# 2_-_Sense2GoL_V1_2_Main_Board.net
KiCad netlist of a schematic drawn in Altium Designer
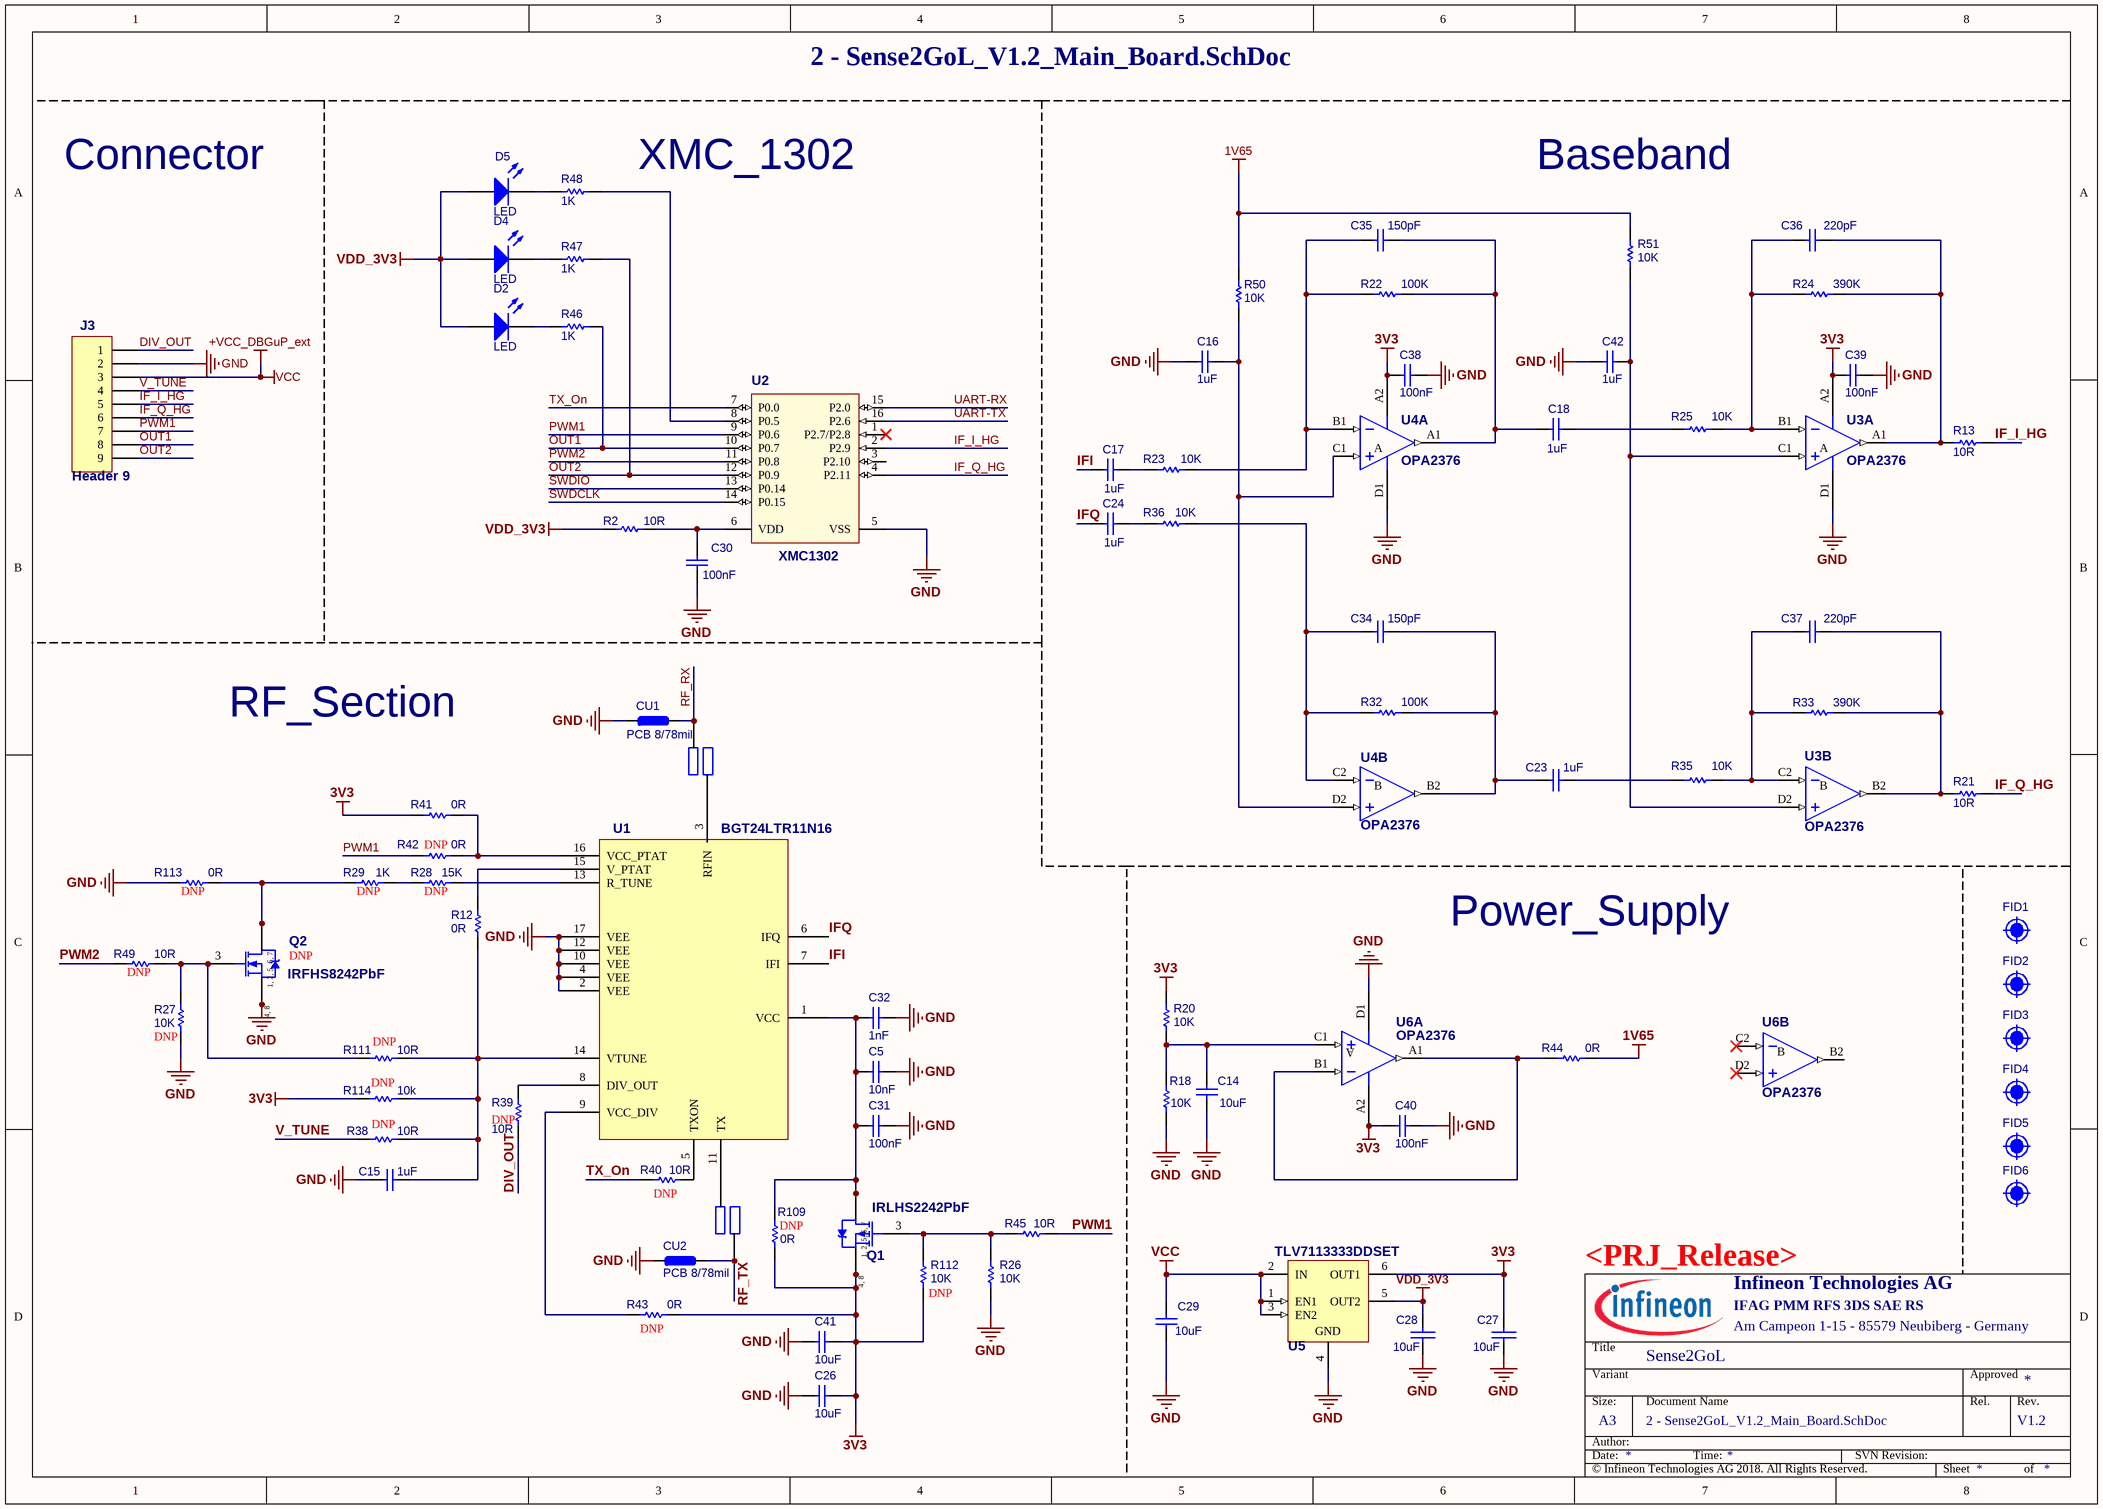
[diagram p0: 2 - Sense2GoL_V1.2_Main_Board.SchDoc]

(export (version "E")
  (design (tool "Eeschema 10.0.6"))
  (components
    (comp (ref "C5")
      (value "10nF")
      (footprint "C_0201")
      (description "Capacitor")
      (fields (field (name "Comment") "Cap") (field (name "PUBLISHER") "Altium Limited"))
      (libsource (lib "Miscellaneous Devices") (part "Cap"))
    )
    (comp (ref "C14")
      (value "10uF")
      (footprint "0402_DURAC")
      (description "Capacitor")
      (fields (field (name "Comment") "Cap") (field (name "PUBLISHER") "Altium Limited"))
      (libsource (lib "Miscellaneous Devices") (part "Cap"))
    )
    (comp (ref "C15")
      (value "1uF")
      (footprint "0402_DURAC")
      (description "Capacitor")
      (fields (field (name "Comment") "Cap") (field (name "PUBLISHER") "Altium Limited"))
      (libsource (lib "Miscellaneous Devices") (part "Cap"))
    )
    (comp (ref "C16")
      (value "1uF")
      (footprint "0402_DURAC")
      (description "Capacitor")
      (fields (field (name "Comment") "Cap") (field (name "PUBLISHER") "Altium Limited"))
      (libsource (lib "Miscellaneous Devices") (part "Cap"))
    )
    (comp (ref "C17")
      (value "1uF")
      (footprint "0402_DURAC")
      (description "Capacitor")
      (fields (field (name "Comment") "1µF") (field (name "PUBLISHER") "Altium Limited"))
      (libsource (lib "Miscellaneous Devices") (part "Cap"))
    )
    (comp (ref "C18")
      (value "1uF")
      (footprint "0402_DURAC")
      (description "Capacitor")
      (fields (field (name "Comment") "Cap") (field (name "PUBLISHER") "Altium Limited"))
      (libsource (lib "Miscellaneous Devices") (part "Cap"))
    )
    (comp (ref "C23")
      (value "1uF")
      (footprint "0402_DURAC")
      (description "Capacitor")
      (fields (field (name "Comment") "Cap") (field (name "PUBLISHER") "Altium Limited"))
      (libsource (lib "Miscellaneous Devices") (part "Cap"))
    )
    (comp (ref "C24")
      (value "1uF")
      (footprint "0402_DURAC")
      (description "Capacitor")
      (fields (field (name "Comment") "Cap") (field (name "PUBLISHER") "Altium Limited"))
      (libsource (lib "Miscellaneous Devices") (part "Cap"))
    )
    (comp (ref "C26")
      (value "10uF")
      (footprint "0402_DURAC")
      (description "Capacitor")
      (fields (field (name "Comment") "Cap") (field (name "PUBLISHER") "Altium Limited"))
      (libsource (lib "Miscellaneous Devices") (part "Cap"))
    )
    (comp (ref "C27")
      (value "10uF")
      (footprint "0402_DURAC")
      (description "Ceramic Capacitor X5R/X7R >= 10V")
      (fields (field (name "MANUFACTURER") "TDK") (field (name "Comment") "CAP-10uF-10V-20%-0603"))
      (libsource (lib "*") (part "CAP"))
    )
    (comp (ref "C28")
      (value "10uF")
      (footprint "0402_DURAC")
      (description "Ceramic Capacitor X5R/X7R >= 10V")
      (fields (field (name "MANUFACTURER") "TDK") (field (name "Comment") "CAP-10uF-10V-20%-0603"))
      (libsource (lib "*") (part "CAP"))
    )
    (comp (ref "C29")
      (value "10uF")
      (footprint "0402_DURAC")
      (description "Capacitor")
      (fields (field (name "MANUFACTURER") "TDK") (field (name "Comment") "CAP-1uF-25V-10%-0402"))
      (libsource (lib "Miscellaneous Devices") (part "Cap"))
    )
    (comp (ref "C30")
      (value "100nF")
      (footprint "C_0201")
      (description "Capacitor")
      (fields (field (name "Comment") "Cap") (field (name "PUBLISHER") "Altium Limited"))
      (libsource (lib "Miscellaneous Devices") (part "Cap"))
    )
    (comp (ref "C31")
      (value "100nF")
      (footprint "C_0201")
      (description "Capacitor")
      (fields (field (name "Comment") "Cap") (field (name "PUBLISHER") "Altium Limited"))
      (libsource (lib "Miscellaneous Devices") (part "Cap"))
    )
    (comp (ref "C32")
      (value "1nF")
      (footprint "C_0201")
      (description "Capacitor")
      (fields (field (name "Comment") "Cap") (field (name "PUBLISHER") "Altium Limited"))
      (libsource (lib "Miscellaneous Devices") (part "Cap"))
    )
    (comp (ref "C34")
      (value "150pF")
      (footprint "C_0201")
      (description "Capacitor")
      (fields (field (name "Comment") "Cap") (field (name "PUBLISHER") "Altium Limited"))
      (libsource (lib "Miscellaneous Devices") (part "Cap"))
    )
    (comp (ref "C35")
      (value "150pF")
      (footprint "C_0201")
      (description "Capacitor")
      (fields (field (name "Comment") "Cap") (field (name "PUBLISHER") "Altium Limited"))
      (libsource (lib "Miscellaneous Devices") (part "Cap"))
    )
    (comp (ref "C36")
      (value "220pF")
      (footprint "C_0201")
      (description "Capacitor")
      (fields (field (name "Comment") "Cap") (field (name "PUBLISHER") "Altium Limited"))
      (libsource (lib "Miscellaneous Devices") (part "Cap"))
    )
    (comp (ref "C37")
      (value "220pF")
      (footprint "C_0201")
      (description "Capacitor")
      (fields (field (name "Comment") "Cap") (field (name "PUBLISHER") "Altium Limited"))
      (libsource (lib "Miscellaneous Devices") (part "Cap"))
    )
    (comp (ref "C38")
      (value "100nF")
      (footprint "C_0201")
      (description "Capacitor")
      (fields (field (name "Comment") "Cap") (field (name "PUBLISHER") "Altium Limited"))
      (libsource (lib "Miscellaneous Devices") (part "Cap"))
    )
    (comp (ref "C39")
      (value "100nF")
      (footprint "C_0201")
      (description "Capacitor")
      (fields (field (name "Comment") "Cap") (field (name "PUBLISHER") "Altium Limited"))
      (libsource (lib "Miscellaneous Devices") (part "Cap"))
    )
    (comp (ref "C40")
      (value "100nF")
      (footprint "C_0201")
      (description "Capacitor")
      (fields (field (name "Comment") "Cap") (field (name "PUBLISHER") "Altium Limited"))
      (libsource (lib "Miscellaneous Devices") (part "Cap"))
    )
    (comp (ref "C41")
      (value "10uF")
      (footprint "0402_DURAC")
      (description "Capacitor")
      (fields (field (name "Comment") "Cap") (field (name "PUBLISHER") "Altium Limited"))
      (libsource (lib "Miscellaneous Devices") (part "Cap"))
    )
    (comp (ref "C42")
      (value "1uF")
      (footprint "0402_DURAC")
      (description "Capacitor")
      (fields (field (name "Comment") "Cap") (field (name "PUBLISHER") "Altium Limited"))
      (libsource (lib "Miscellaneous Devices") (part "Cap"))
    )
    (comp (ref "CU1")
      (value "PCB 8/78mil")
      (footprint "24GHZ_TRACE_8_78")
      (libsource (lib "Miscellaneous Devices") (part "24G_Trace"))
    )
    (comp (ref "CU2")
      (value "PCB 8/78mil")
      (footprint "24GHZ_TRACE_8_78")
      (libsource (lib "Miscellaneous Devices") (part "24G_Trace"))
    )
    (comp (ref "D2")
      (value "LED")
      (footprint "LED_0201")
      (description "Typical INFRARED GaAs LED")
      (fields (field (name "PUBLISHER") "Altium Limited"))
      (libsource (lib "Miscellaneous Devices") (part "LED"))
    )
    (comp (ref "D4")
      (value "LED")
      (footprint "LED_0201")
      (description "Typical INFRARED GaAs LED")
      (fields (field (name "PUBLISHER") "Altium Limited"))
      (libsource (lib "Miscellaneous Devices") (part "LED"))
    )
    (comp (ref "D5")
      (value "LED")
      (footprint "LED_0201")
      (description "Typical INFRARED GaAs LED")
      (fields (field (name "PUBLISHER") "Altium Limited"))
      (libsource (lib "Miscellaneous Devices") (part "LED"))
    )
    (comp (ref "DC1")
      (value "HF-Bandbpass")
      (footprint "DC_BLOCK_24GHZ")
      (libsource (lib "Miscellaneous Devices") (part "HF-Bandbpass"))
    )
    (comp (ref "DC2")
      (value "HF-Bandbpass")
      (footprint "DC_BLOCK_24GHZ")
      (libsource (lib "Miscellaneous Devices") (part "HF-Bandbpass"))
    )
    (comp (ref "FID1")
      (value "Fiducial")
      (footprint "FID_1.1mm")
      (libsource (lib "Miscellaneous Devices") (part "FID"))
    )
    (comp (ref "FID2")
      (value "Fiducial")
      (footprint "FID_1.1mm")
      (libsource (lib "Miscellaneous Devices") (part "FID"))
    )
    (comp (ref "FID3")
      (value "Fiducial")
      (footprint "FID_1.1mm")
      (libsource (lib "Miscellaneous Devices") (part "FID"))
    )
    (comp (ref "FID4")
      (value "Fiducial")
      (footprint "FID_1.1mm")
      (libsource (lib "Miscellaneous Devices") (part "FID"))
    )
    (comp (ref "FID5")
      (value "Fiducial")
      (footprint "FID_1.1mm")
      (libsource (lib "Miscellaneous Devices") (part "FID"))
    )
    (comp (ref "FID6")
      (value "Fiducial")
      (footprint "FID_1.1mm")
      (libsource (lib "Miscellaneous Devices") (part "FID"))
    )
    (comp (ref "J3")
      (value "Header 9")
      (footprint "CONN_9_90DEG_TH")
      (description "Header, 9-Pin")
      (fields (field (name "PUBLISHER") "Altium Limited"))
      (libsource (lib "Miscellaneous Connectors") (part "Header 9"))
    )
    (comp (ref "Q1")
      (value "IRLHS2242PbF")
      (footprint "IRLSH2242")
      (fields (field (name "PUBLISHER") "Altium Limited"))
      (libsource (lib "Integrated Circuits") (part "IRLHS2242PbF"))
    )
    (comp (ref "Q2")
      (value "IRFHS8242PbF")
      (footprint "IRLSH2242")
      (fields (field (name "Comment") "DNP") (field (name "PUBLISHER") "Altium Limited"))
      (libsource (lib "Integrated Circuits") (part "IRLHS8242PbF"))
    )
    (comp (ref "R2")
      (value "10R")
      (footprint "R_0201")
      (description "Resistor")
      (fields (field (name "Comment") "Res1") (field (name "PUBLISHER") "Altium Limited"))
      (libsource (lib "Miscellaneous Devices") (part "Res1"))
    )
    (comp (ref "R12")
      (value "0R")
      (footprint "R_0201")
      (description "Resistor")
      (fields (field (name "Comment") "Res1") (field (name "PUBLISHER") "Altium Limited"))
      (libsource (lib "Miscellaneous Devices") (part "Res1"))
    )
    (comp (ref "R13")
      (value "10R")
      (footprint "R_0201")
      (description "Resistor")
      (fields (field (name "Comment") "Res1") (field (name "PUBLISHER") "Altium Limited"))
      (libsource (lib "Miscellaneous Devices") (part "Res1"))
    )
    (comp (ref "R18")
      (value "10K")
      (footprint "R_0201")
      (description "Resistor")
      (fields (field (name "Comment") "Res1") (field (name "PUBLISHER") "Altium Limited"))
      (libsource (lib "Miscellaneous Devices") (part "Res1"))
    )
    (comp (ref "R20")
      (value "10K")
      (footprint "R_0201")
      (description "Resistor")
      (fields (field (name "Comment") "Res1") (field (name "PUBLISHER") "Altium Limited"))
      (libsource (lib "Miscellaneous Devices") (part "Res1"))
    )
    (comp (ref "R21")
      (value "10R")
      (footprint "R_0201")
      (description "Resistor")
      (fields (field (name "Comment") "Res1") (field (name "PUBLISHER") "Altium Limited"))
      (libsource (lib "Miscellaneous Devices") (part "Res1"))
    )
    (comp (ref "R22")
      (value "100K")
      (footprint "R_0201")
      (description "Resistor")
      (fields (field (name "Comment") "Res1") (field (name "PUBLISHER") "Altium Limited"))
      (libsource (lib "Miscellaneous Devices") (part "Res1"))
    )
    (comp (ref "R23")
      (value "10K")
      (footprint "R_0201")
      (description "Resistor")
      (fields (field (name "Comment") "Res1") (field (name "PUBLISHER") "Altium Limited"))
      (libsource (lib "Miscellaneous Devices") (part "Res1"))
    )
    (comp (ref "R24")
      (value "390K")
      (footprint "R_0201")
      (description "Resistor")
      (fields (field (name "Comment") "Res1") (field (name "PUBLISHER") "Altium Limited"))
      (libsource (lib "Miscellaneous Devices") (part "Res1"))
    )
    (comp (ref "R25")
      (value "10K")
      (footprint "R_0201")
      (description "Resistor")
      (fields (field (name "Comment") "Res1") (field (name "PUBLISHER") "Altium Limited"))
      (libsource (lib "Miscellaneous Devices") (part "Res1"))
    )
    (comp (ref "R26")
      (value "10K")
      (footprint "R_0201")
      (description "Resistor")
      (fields (field (name "Comment") "Res1") (field (name "PUBLISHER") "Altium Limited"))
      (libsource (lib "Miscellaneous Devices") (part "Res1"))
    )
    (comp (ref "R27")
      (value "10K")
      (footprint "R_0201")
      (description "Resistor")
      (fields (field (name "Comment") "DNP") (field (name "PUBLISHER") "Altium Limited"))
      (libsource (lib "Miscellaneous Devices") (part "Res1"))
    )
    (comp (ref "R28")
      (value "15K")
      (footprint "R_0201")
      (description "Resistor")
      (fields (field (name "Comment") "DNP") (field (name "PUBLISHER") "Altium Limited"))
      (libsource (lib "Miscellaneous Devices") (part "Res1"))
    )
    (comp (ref "R29")
      (value "1K")
      (footprint "R_0201")
      (description "Resistor")
      (fields (field (name "Comment") "DNP") (field (name "PUBLISHER") "Altium Limited"))
      (libsource (lib "Miscellaneous Devices") (part "Res1"))
    )
    (comp (ref "R32")
      (value "100K")
      (footprint "R_0201")
      (description "Resistor")
      (fields (field (name "Comment") "Res1") (field (name "PUBLISHER") "Altium Limited"))
      (libsource (lib "Miscellaneous Devices") (part "Res1"))
    )
    (comp (ref "R33")
      (value "390K")
      (footprint "R_0201")
      (description "Resistor")
      (fields (field (name "Comment") "Res1") (field (name "PUBLISHER") "Altium Limited"))
      (libsource (lib "Miscellaneous Devices") (part "Res1"))
    )
    (comp (ref "R35")
      (value "10K")
      (footprint "R_0201")
      (description "Resistor")
      (fields (field (name "Comment") "Res1") (field (name "PUBLISHER") "Altium Limited"))
      (libsource (lib "Miscellaneous Devices") (part "Res1"))
    )
    (comp (ref "R36")
      (value "10K")
      (footprint "R_0201")
      (description "Resistor")
      (fields (field (name "Comment") "Res1") (field (name "PUBLISHER") "Altium Limited"))
      (libsource (lib "Miscellaneous Devices") (part "Res1"))
    )
    (comp (ref "R38")
      (value "10R")
      (footprint "R_0201")
      (description "Resistor")
      (fields (field (name "Comment") "DNP") (field (name "PUBLISHER") "Altium Limited"))
      (libsource (lib "Miscellaneous Devices") (part "Res1"))
    )
    (comp (ref "R39")
      (value "10R")
      (footprint "R_0201")
      (description "Resistor")
      (fields (field (name "Comment") "DNP") (field (name "PUBLISHER") "Altium Limited"))
      (libsource (lib "Miscellaneous Devices") (part "Res1"))
    )
    (comp (ref "R40")
      (value "10R")
      (footprint "R_0201")
      (description "Resistor")
      (fields (field (name "Comment") "DNP") (field (name "PUBLISHER") "Altium Limited"))
      (libsource (lib "Miscellaneous Devices") (part "Res1"))
    )
    (comp (ref "R41")
      (value "0R")
      (footprint "R_0201")
      (description "Resistor")
      (fields (field (name "Comment") "Res1") (field (name "PUBLISHER") "Altium Limited"))
      (libsource (lib "Miscellaneous Devices") (part "Res1"))
    )
    (comp (ref "R42")
      (value "0R")
      (footprint "R_0201")
      (description "Resistor")
      (fields (field (name "Comment") "DNP") (field (name "PUBLISHER") "Altium Limited"))
      (libsource (lib "Miscellaneous Devices") (part "Res1"))
    )
    (comp (ref "R43")
      (value "0R")
      (footprint "R_0201")
      (description "Resistor")
      (fields (field (name "Comment") "DNP") (field (name "PUBLISHER") "Altium Limited"))
      (libsource (lib "Miscellaneous Devices") (part "Res1"))
    )
    (comp (ref "R44")
      (value "0R")
      (footprint "R_0201")
      (description "Resistor")
      (fields (field (name "Comment") "Res1") (field (name "PUBLISHER") "Altium Limited"))
      (libsource (lib "Miscellaneous Devices") (part "Res1"))
    )
    (comp (ref "R45")
      (value "10R")
      (footprint "R_0201")
      (description "Resistor")
      (fields (field (name "Comment") "Res1") (field (name "PUBLISHER") "Altium Limited"))
      (libsource (lib "Miscellaneous Devices") (part "Res1"))
    )
    (comp (ref "R46")
      (value "1K")
      (footprint "R_0201")
      (description "Resistor")
      (fields (field (name "Comment") "Res1") (field (name "PUBLISHER") "Altium Limited"))
      (libsource (lib "Miscellaneous Devices") (part "Res1"))
    )
    (comp (ref "R47")
      (value "1K")
      (footprint "R_0201")
      (description "Resistor")
      (fields (field (name "Comment") "Res1") (field (name "PUBLISHER") "Altium Limited"))
      (libsource (lib "Miscellaneous Devices") (part "Res1"))
    )
    (comp (ref "R48")
      (value "1K")
      (footprint "R_0201")
      (description "Resistor")
      (fields (field (name "Comment") "Res1") (field (name "PUBLISHER") "Altium Limited"))
      (libsource (lib "Miscellaneous Devices") (part "Res1"))
    )
    (comp (ref "R49")
      (value "10R")
      (footprint "R_0201")
      (description "Resistor")
      (fields (field (name "Comment") "DNP") (field (name "PUBLISHER") "Altium Limited"))
      (libsource (lib "Miscellaneous Devices") (part "Res1"))
    )
    (comp (ref "R50")
      (value "10K")
      (footprint "R_0201")
      (description "Resistor")
      (fields (field (name "Comment") "Res1") (field (name "PUBLISHER") "Altium Limited"))
      (libsource (lib "Miscellaneous Devices") (part "Res1"))
    )
    (comp (ref "R51")
      (value "10K")
      (footprint "R_0201")
      (description "Resistor")
      (fields (field (name "Comment") "Res1") (field (name "PUBLISHER") "Altium Limited"))
      (libsource (lib "Miscellaneous Devices") (part "Res1"))
    )
    (comp (ref "R109")
      (value "0R")
      (footprint "R_0201")
      (description "Resistor")
      (fields (field (name "Comment") "DNP") (field (name "PUBLISHER") "Altium Limited"))
      (libsource (lib "Miscellaneous Devices") (part "Res1"))
    )
    (comp (ref "R111")
      (value "10R")
      (footprint "R_0201")
      (description "Resistor")
      (fields (field (name "Comment") "DNP") (field (name "PUBLISHER") "Altium Limited"))
      (libsource (lib "Miscellaneous Devices") (part "Res1"))
    )
    (comp (ref "R112")
      (value "10K")
      (footprint "R_0201")
      (description "Resistor")
      (fields (field (name "Comment") "DNP") (field (name "PUBLISHER") "Altium Limited"))
      (libsource (lib "Miscellaneous Devices") (part "Res1"))
    )
    (comp (ref "R113")
      (value "0R")
      (footprint "R_0201")
      (description "Resistor")
      (fields (field (name "Comment") "DNP") (field (name "PUBLISHER") "Altium Limited"))
      (libsource (lib "Miscellaneous Devices") (part "Res1"))
    )
    (comp (ref "R114")
      (value "10k")
      (footprint "R_0201")
      (description "Resistor")
      (fields (field (name "Comment") "DNP") (field (name "PUBLISHER") "Altium Limited"))
      (libsource (lib "Miscellaneous Devices") (part "Res1"))
    )
    (comp (ref "U1")
      (value "BGT24LTR11N16")
      (footprint "TSNP-16-9")
      (libsource (lib "BGT24") (part "BGT24LTR11N16"))
    )
    (comp (ref "U2")
      (value "XMC1302")
      (footprint "inf-pg-tssop-16-8_n")
      (libsource (lib "Integrated Circuits") (part "XMC1302-T016F-0016 AA"))
    )
    (comp (ref "U3")
      (value "OPA2376")
      (footprint "OPA2376_DSBGA")
      (fields (field (name "PUBLISHER") "Altium Limited"))
      (libsource (lib "Integrated Circuits") (part "OPA2376"))
    )
    (comp (ref "U4")
      (value "OPA2376")
      (footprint "OPA2376_DSBGA")
      (fields (field (name "PUBLISHER") "Altium Limited"))
      (libsource (lib "Integrated Circuits") (part "OPA2376"))
    )
    (comp (ref "U5")
      (value "TLV7113333DDSET")
      (footprint "TLV7113333")
      (fields (field (name "MANUFACTURER") "Texas Instruments"))
      (libsource (lib "Integrated Circuits") (part "TLV7113333DDSET"))
    )
    (comp (ref "U6")
      (value "OPA2376")
      (footprint "OPA2376_DSBGA")
      (fields (field (name "PUBLISHER") "Altium Limited"))
      (libsource (lib "Integrated Circuits") (part "OPA2376"))
    )
  )
  (nets
    (net (code "1") (name "+VCC_DBGuP_ext") (class "Default")
      (node (ref "C29") (pin "1") (pinfunction "1_1") (pintype "passive"))
      (node (ref "J3") (pin "3") (pinfunction "3_3") (pintype "passive"))
      (node (ref "U5") (pin "1") (pinfunction "EN1_1") (pintype "input"))
      (node (ref "U5") (pin "2") (pinfunction "IN_2") (pintype "power_in"))
      (node (ref "U5") (pin "3") (pinfunction "EN2_3") (pintype "input"))
    )
    (net (code "2") (name "/DIV_OUT") (class "Default")
      (node (ref "J3") (pin "1") (pinfunction "1_1") (pintype "passive"))
      (node (ref "R39") (pin "1") (pinfunction "1_1") (pintype "passive"))
    )
    (net (code "3") (name "/IFI") (class "Default")
      (node (ref "C17") (pin "1") (pinfunction "1_1") (pintype "passive"))
      (node (ref "U1") (pin "7") (pinfunction "IFI_7") (pintype "passive"))
    )
    (net (code "4") (name "/IFQ") (class "Default")
      (node (ref "C24") (pin "1") (pinfunction "1_1") (pintype "passive"))
      (node (ref "U1") (pin "6") (pinfunction "IFQ_6") (pintype "passive"))
    )
    (net (code "5") (name "/IF_I_HG") (class "Default")
      (node (ref "J3") (pin "5") (pinfunction "5_5") (pintype "passive"))
      (node (ref "R13") (pin "2") (pinfunction "2_2") (pintype "passive"))
      (node (ref "U2") (pin "2") (pinfunction "P2.9_2") (pintype "input"))
    )
    (net (code "6") (name "/IF_Q_HG") (class "Default")
      (node (ref "J3") (pin "6") (pinfunction "6_6") (pintype "passive"))
      (node (ref "R21") (pin "2") (pinfunction "2_2") (pintype "passive"))
      (node (ref "U2") (pin "4") (pinfunction "P2.11_4") (pintype "bidirectional"))
    )
    (net (code "7") (name "/OUT1") (class "Default")
      (node (ref "J3") (pin "8") (pinfunction "8_8") (pintype "passive"))
      (node (ref "R46") (pin "2") (pinfunction "2_2") (pintype "passive"))
      (node (ref "U2") (pin "10") (pinfunction "P0.7_10") (pintype "bidirectional"))
    )
    (net (code "8") (name "/OUT2") (class "Default")
      (node (ref "J3") (pin "9") (pinfunction "9_9") (pintype "passive"))
      (node (ref "R47") (pin "2") (pinfunction "2_2") (pintype "passive"))
      (node (ref "U2") (pin "12") (pinfunction "P0.9_12") (pintype "bidirectional"))
    )
    (net (code "9") (name "/PWM1") (class "Default")
      (node (ref "J3") (pin "7") (pinfunction "7_7") (pintype "passive"))
      (node (ref "R42") (pin "1") (pinfunction "1_1") (pintype "passive"))
      (node (ref "R45") (pin "2") (pinfunction "2_2") (pintype "passive"))
      (node (ref "U2") (pin "9") (pinfunction "P0.6_9") (pintype "bidirectional"))
    )
    (net (code "10") (name "/PWM2") (class "Default")
      (node (ref "R49") (pin "1") (pinfunction "1_1") (pintype "passive"))
      (node (ref "U2") (pin "11") (pinfunction "P0.8_11") (pintype "bidirectional"))
    )
    (net (code "11") (name "/RF_RX") (class "Default")
      (node (ref "CU1") (pin "1") (pinfunction "1_1") (pintype "passive"))
      (node (ref "DC2") (pin "1") (pinfunction "1_1") (pintype "passive"))
    )
    (net (code "12") (name "/RF_TX") (class "Default")
      (node (ref "CU2") (pin "1") (pinfunction "1_1") (pintype "passive"))
      (node (ref "DC1") (pin "1") (pinfunction "1_1") (pintype "passive"))
    )
    (net (code "13") (name "/SWDCLK") (class "Default")
      (node (ref "U2") (pin "14") (pinfunction "P0.15_14") (pintype "bidirectional"))
    )
    (net (code "14") (name "/SWDIO") (class "Default")
      (node (ref "U2") (pin "13") (pinfunction "P0.14_13") (pintype "bidirectional"))
    )
    (net (code "15") (name "/TX_On") (class "Default")
      (node (ref "R40") (pin "1") (pinfunction "1_1") (pintype "passive"))
      (node (ref "U2") (pin "7") (pinfunction "P0.0_7") (pintype "bidirectional"))
    )
    (net (code "16") (name "/UART-RX") (class "Default")
      (node (ref "U2") (pin "15") (pinfunction "P2.0_15") (pintype "bidirectional"))
    )
    (net (code "17") (name "/UART-TX") (class "Default")
      (node (ref "U2") (pin "16") (pinfunction "P2.6_16") (pintype "input"))
    )
    (net (code "18") (name "/V_TUNE") (class "Default")
      (node (ref "J3") (pin "4") (pinfunction "4_4") (pintype "passive"))
      (node (ref "R38") (pin "1") (pinfunction "1_1") (pintype "passive"))
    )
    (net (code "19") (name "1V65") (class "Default")
      (node (ref "R44") (pin "2") (pinfunction "2_2") (pintype "passive"))
      (node (ref "R50") (pin "1") (pinfunction "1_1") (pintype "passive"))
      (node (ref "R51") (pin "1") (pinfunction "1_1") (pintype "passive"))
    )
    (net (code "20") (name "3V3") (class "Default")
      (node (ref "C26") (pin "2") (pinfunction "2_2") (pintype "passive"))
      (node (ref "C27") (pin "1") (pinfunction "1_1") (pintype "passive"))
      (node (ref "C38") (pin "1") (pinfunction "1_1") (pintype "passive"))
      (node (ref "C39") (pin "1") (pinfunction "1_1") (pintype "passive"))
      (node (ref "C40") (pin "1") (pinfunction "1_1") (pintype "passive"))
      (node (ref "C41") (pin "2") (pinfunction "2_2") (pintype "passive"))
      (node (ref "Q1") (pin "4") (pinfunction "S_4") (pintype "passive"))
      (node (ref "Q1") (pin "8") (pinfunction "S_8") (pintype "passive"))
      (node (ref "R109") (pin "1") (pinfunction "1_1") (pintype "passive"))
      (node (ref "R112") (pin "1") (pinfunction "1_1") (pintype "passive"))
      (node (ref "R114") (pin "1") (pinfunction "1_1") (pintype "passive"))
      (node (ref "R20") (pin "2") (pinfunction "2_2") (pintype "passive"))
      (node (ref "R41") (pin "1") (pinfunction "1_1") (pintype "passive"))
      (node (ref "R43") (pin "2") (pinfunction "2_2") (pintype "passive"))
      (node (ref "U3") (pin "A2") (pinfunction "V+_A2") (pintype "passive"))
      (node (ref "U4") (pin "A2") (pinfunction "V+_A2") (pintype "passive"))
      (node (ref "U5") (pin "6") (pinfunction "OUT1_6") (pintype "power_in"))
      (node (ref "U6") (pin "A2") (pinfunction "V+_A2") (pintype "passive"))
    )
    (net (code "21") (name "GND") (class "Default")
      (node (ref "C14") (pin "2") (pinfunction "2_2") (pintype "passive"))
      (node (ref "C15") (pin "1") (pinfunction "1_1") (pintype "passive"))
      (node (ref "C16") (pin "1") (pinfunction "1_1") (pintype "passive"))
      (node (ref "C26") (pin "1") (pinfunction "1_1") (pintype "passive"))
      (node (ref "C27") (pin "2") (pinfunction "2_2") (pintype "passive"))
      (node (ref "C28") (pin "2") (pinfunction "2_2") (pintype "passive"))
      (node (ref "C29") (pin "2") (pinfunction "2_2") (pintype "passive"))
      (node (ref "C30") (pin "2") (pinfunction "2_2") (pintype "passive"))
      (node (ref "C31") (pin "2") (pinfunction "2_2") (pintype "passive"))
      (node (ref "C32") (pin "2") (pinfunction "2_2") (pintype "passive"))
      (node (ref "C38") (pin "2") (pinfunction "2_2") (pintype "passive"))
      (node (ref "C39") (pin "2") (pinfunction "2_2") (pintype "passive"))
      (node (ref "C40") (pin "2") (pinfunction "2_2") (pintype "passive"))
      (node (ref "C41") (pin "1") (pinfunction "1_1") (pintype "passive"))
      (node (ref "C42") (pin "1") (pinfunction "1_1") (pintype "passive"))
      (node (ref "C5") (pin "2") (pinfunction "2_2") (pintype "passive"))
      (node (ref "CU1") (pin "2") (pinfunction "2_2") (pintype "passive"))
      (node (ref "CU2") (pin "2") (pinfunction "2_2") (pintype "passive"))
      (node (ref "J3") (pin "2") (pinfunction "2_2") (pintype "passive"))
      (node (ref "Q2") (pin "4") (pinfunction "S_4") (pintype "passive"))
      (node (ref "Q2") (pin "8") (pinfunction "S_8") (pintype "passive"))
      (node (ref "R113") (pin "1") (pinfunction "1_1") (pintype "passive"))
      (node (ref "R18") (pin "1") (pinfunction "1_1") (pintype "passive"))
      (node (ref "R26") (pin "1") (pinfunction "1_1") (pintype "passive"))
      (node (ref "R27") (pin "1") (pinfunction "1_1") (pintype "passive"))
      (node (ref "U1") (pin "10") (pinfunction "VEE_10") (pintype "passive"))
      (node (ref "U1") (pin "12") (pinfunction "VEE_12") (pintype "passive"))
      (node (ref "U1") (pin "17") (pinfunction "VEE_17") (pintype "passive"))
      (node (ref "U1") (pin "2") (pinfunction "VEE_2") (pintype "passive"))
      (node (ref "U1") (pin "4") (pinfunction "VEE_4") (pintype "passive"))
      (node (ref "U2") (pin "5") (pinfunction "VSS_5") (pintype "power_in"))
      (node (ref "U3") (pin "D1") (pinfunction "V-_D1") (pintype "passive"))
      (node (ref "U4") (pin "D1") (pinfunction "V-_D1") (pintype "passive"))
      (node (ref "U5") (pin "4") (pinfunction "GND_4") (pintype "power_in"))
      (node (ref "U6") (pin "D1") (pinfunction "V-_D1") (pintype "passive"))
    )
    (net (code "22") (name "Net-(C17-Pad2)") (class "Default")
      (node (ref "C17") (pin "2") (pinfunction "2_2") (pintype "passive"))
      (node (ref "R23") (pin "1") (pinfunction "1_1") (pintype "passive"))
    )
    (net (code "23") (name "Net-(C18-Pad2)") (class "Default")
      (node (ref "C18") (pin "2") (pinfunction "2_2") (pintype "passive"))
      (node (ref "R25") (pin "1") (pinfunction "1_1") (pintype "passive"))
    )
    (net (code "24") (name "Net-(C23-Pad2)") (class "Default")
      (node (ref "C23") (pin "2") (pinfunction "2_2") (pintype "passive"))
      (node (ref "R35") (pin "1") (pinfunction "1_1") (pintype "passive"))
    )
    (net (code "25") (name "Net-(C24-Pad2)") (class "Default")
      (node (ref "C24") (pin "2") (pinfunction "2_2") (pintype "passive"))
      (node (ref "R36") (pin "1") (pinfunction "1_1") (pintype "passive"))
    )
    (net (code "26") (name "Net-(D2-K)") (class "Default")
      (node (ref "D2") (pin "2") (pinfunction "K_2") (pintype "passive"))
      (node (ref "R46") (pin "1") (pinfunction "1_1") (pintype "passive"))
    )
    (net (code "27") (name "Net-(D4-K)") (class "Default")
      (node (ref "D4") (pin "2") (pinfunction "K_2") (pintype "passive"))
      (node (ref "R47") (pin "1") (pinfunction "1_1") (pintype "passive"))
    )
    (net (code "28") (name "Net-(D5-K)") (class "Default")
      (node (ref "D5") (pin "2") (pinfunction "K_2") (pintype "passive"))
      (node (ref "R48") (pin "1") (pinfunction "1_1") (pintype "passive"))
    )
    (net (code "29") (name "Net-(Q1-G)") (class "Default")
      (node (ref "Q1") (pin "3") (pinfunction "G_3") (pintype "passive"))
      (node (ref "R112") (pin "2") (pinfunction "2_2") (pintype "passive"))
      (node (ref "R26") (pin "2") (pinfunction "2_2") (pintype "passive"))
      (node (ref "R45") (pin "1") (pinfunction "1_1") (pintype "passive"))
    )
    (net (code "30") (name "Net-(Q2-D-Pad1)") (class "Default")
      (node (ref "Q2") (pin "1") (pinfunction "D_1") (pintype "passive"))
      (node (ref "Q2") (pin "2") (pinfunction "D_2") (pintype "passive"))
      (node (ref "Q2") (pin "5") (pinfunction "D_5") (pintype "passive"))
      (node (ref "Q2") (pin "6") (pinfunction "D_6") (pintype "passive"))
      (node (ref "Q2") (pin "7") (pinfunction "D_7") (pintype "passive"))
      (node (ref "R113") (pin "2") (pinfunction "2_2") (pintype "passive"))
      (node (ref "R29") (pin "1") (pinfunction "1_1") (pintype "passive"))
    )
    (net (code "31") (name "Net-(Q2-G)") (class "Default")
      (node (ref "Q2") (pin "3") (pinfunction "G_3") (pintype "passive"))
      (node (ref "R111") (pin "1") (pinfunction "1_1") (pintype "passive"))
      (node (ref "R27") (pin "2") (pinfunction "2_2") (pintype "passive"))
      (node (ref "R49") (pin "2") (pinfunction "2_2") (pintype "passive"))
    )
    (net (code "32") (name "Net-(R28-Pad1)") (class "Default")
      (node (ref "R28") (pin "1") (pinfunction "1_1") (pintype "passive"))
      (node (ref "R29") (pin "2") (pinfunction "2_2") (pintype "passive"))
    )
    (net (code "33") (name "Net-(U1-DIV_OUT)") (class "Default")
      (node (ref "R39") (pin "2") (pinfunction "2_2") (pintype "passive"))
      (node (ref "U1") (pin "8") (pinfunction "DIV_OUT_8") (pintype "passive"))
    )
    (net (code "34") (name "Net-(U1-RFIN)") (class "Default")
      (node (ref "DC2") (pin "2") (pinfunction "2_2") (pintype "passive"))
      (node (ref "U1") (pin "3") (pinfunction "RFIN_3") (pintype "passive"))
    )
    (net (code "35") (name "Net-(U1-R_TUNE)") (class "Default")
      (node (ref "R28") (pin "2") (pinfunction "2_2") (pintype "passive"))
      (node (ref "U1") (pin "13") (pinfunction "R_TUNE_13") (pintype "passive"))
    )
    (net (code "36") (name "Net-(U1-TX)") (class "Default")
      (node (ref "DC1") (pin "2") (pinfunction "2_2") (pintype "passive"))
      (node (ref "U1") (pin "11") (pinfunction "TX_11") (pintype "passive"))
    )
    (net (code "37") (name "Net-(U1-TXON)") (class "Default")
      (node (ref "R40") (pin "2") (pinfunction "2_2") (pintype "passive"))
      (node (ref "U1") (pin "5") (pinfunction "TXON_5") (pintype "passive"))
    )
    (net (code "38") (name "Net-(U1-VCC)") (class "Default")
      (node (ref "C31") (pin "1") (pinfunction "1_1") (pintype "passive"))
      (node (ref "C32") (pin "1") (pinfunction "1_1") (pintype "passive"))
      (node (ref "C5") (pin "1") (pinfunction "1_1") (pintype "passive"))
      (node (ref "Q1") (pin "1") (pinfunction "D_1") (pintype "passive"))
      (node (ref "Q1") (pin "2") (pinfunction "D_2") (pintype "passive"))
      (node (ref "Q1") (pin "5") (pinfunction "D_5") (pintype "passive"))
      (node (ref "Q1") (pin "6") (pinfunction "D_6") (pintype "passive"))
      (node (ref "Q1") (pin "7") (pinfunction "D_7") (pintype "passive"))
      (node (ref "R109") (pin "2") (pinfunction "2_2") (pintype "passive"))
      (node (ref "U1") (pin "1") (pinfunction "VCC_1") (pintype "passive"))
    )
    (net (code "39") (name "Net-(U1-VCC_DIV)") (class "Default")
      (node (ref "R43") (pin "1") (pinfunction "1_1") (pintype "passive"))
      (node (ref "U1") (pin "9") (pinfunction "VCC_DIV_9") (pintype "passive"))
    )
    (net (code "40") (name "Net-(U1-VCC_PTAT)") (class "Default")
      (node (ref "R41") (pin "2") (pinfunction "2_2") (pintype "passive"))
      (node (ref "R42") (pin "2") (pinfunction "2_2") (pintype "passive"))
      (node (ref "U1") (pin "16") (pinfunction "VCC_PTAT_16") (pintype "passive"))
    )
    (net (code "41") (name "Net-(U1-VTUNE)") (class "Default")
      (node (ref "C15") (pin "2") (pinfunction "2_2") (pintype "passive"))
      (node (ref "R111") (pin "2") (pinfunction "2_2") (pintype "passive"))
      (node (ref "R114") (pin "2") (pinfunction "2_2") (pintype "passive"))
      (node (ref "R12") (pin "1") (pinfunction "1_1") (pintype "passive"))
      (node (ref "R38") (pin "2") (pinfunction "2_2") (pintype "passive"))
      (node (ref "U1") (pin "14") (pinfunction "VTUNE_14") (pintype "passive"))
    )
    (net (code "42") (name "Net-(U1-V_PTAT)") (class "Default")
      (node (ref "R12") (pin "2") (pinfunction "2_2") (pintype "passive"))
      (node (ref "U1") (pin "15") (pinfunction "V_PTAT_15") (pintype "passive"))
    )
    (net (code "43") (name "Net-(U2-P0.5)") (class "Default")
      (node (ref "R48") (pin "2") (pinfunction "2_2") (pintype "passive"))
      (node (ref "U2") (pin "8") (pinfunction "P0.5_8") (pintype "bidirectional"))
    )
    (net (code "44") (name "Net-(U2-VDD)") (class "Default")
      (node (ref "C30") (pin "1") (pinfunction "1_1") (pintype "passive"))
      (node (ref "R2") (pin "2") (pinfunction "2_2") (pintype "passive"))
      (node (ref "U2") (pin "6") (pinfunction "VDD_6") (pintype "power_in"))
    )
    (net (code "45") (name "Net-(U3A-+INA)") (class "Default")
      (node (ref "C42") (pin "2") (pinfunction "2_2") (pintype "passive"))
      (node (ref "R51") (pin "2") (pinfunction "2_2") (pintype "passive"))
      (node (ref "U3") (pin "C1") (pinfunction "+INA_C1") (pintype "input"))
      (node (ref "U3") (pin "D2") (pinfunction "IN+_D2") (pintype "input"))
    )
    (net (code "46") (name "Net-(U3A--INA)") (class "Default")
      (node (ref "C36") (pin "1") (pinfunction "1_1") (pintype "passive"))
      (node (ref "R24") (pin "1") (pinfunction "1_1") (pintype "passive"))
      (node (ref "R25") (pin "2") (pinfunction "2_2") (pintype "passive"))
      (node (ref "U3") (pin "B1") (pinfunction "-INA_B1") (pintype "input"))
    )
    (net (code "47") (name "Net-(U3A-OUT_A)") (class "Default")
      (node (ref "C36") (pin "2") (pinfunction "2_2") (pintype "passive"))
      (node (ref "R13") (pin "1") (pinfunction "1_1") (pintype "passive"))
      (node (ref "R24") (pin "2") (pinfunction "2_2") (pintype "passive"))
      (node (ref "U3") (pin "A1") (pinfunction "OUT_A_A1") (pintype "output"))
    )
    (net (code "48") (name "Net-(U3B-IN-)") (class "Default")
      (node (ref "C37") (pin "1") (pinfunction "1_1") (pintype "passive"))
      (node (ref "R33") (pin "1") (pinfunction "1_1") (pintype "passive"))
      (node (ref "R35") (pin "2") (pinfunction "2_2") (pintype "passive"))
      (node (ref "U3") (pin "C2") (pinfunction "IN-_C2") (pintype "input"))
    )
    (net (code "49") (name "Net-(U3B-OUT)") (class "Default")
      (node (ref "C37") (pin "2") (pinfunction "2_2") (pintype "passive"))
      (node (ref "R21") (pin "1") (pinfunction "1_1") (pintype "passive"))
      (node (ref "R33") (pin "2") (pinfunction "2_2") (pintype "passive"))
      (node (ref "U3") (pin "B2") (pinfunction "OUT_B2") (pintype "output"))
    )
    (net (code "50") (name "Net-(U4A-+INA)") (class "Default")
      (node (ref "C16") (pin "2") (pinfunction "2_2") (pintype "passive"))
      (node (ref "R50") (pin "2") (pinfunction "2_2") (pintype "passive"))
      (node (ref "U4") (pin "C1") (pinfunction "+INA_C1") (pintype "input"))
      (node (ref "U4") (pin "D2") (pinfunction "IN+_D2") (pintype "input"))
    )
    (net (code "51") (name "Net-(U4A--INA)") (class "Default")
      (node (ref "C35") (pin "1") (pinfunction "1_1") (pintype "passive"))
      (node (ref "R22") (pin "1") (pinfunction "1_1") (pintype "passive"))
      (node (ref "R23") (pin "2") (pinfunction "2_2") (pintype "passive"))
      (node (ref "U4") (pin "B1") (pinfunction "-INA_B1") (pintype "input"))
    )
    (net (code "52") (name "Net-(U4A-OUT_A)") (class "Default")
      (node (ref "C18") (pin "1") (pinfunction "1_1") (pintype "passive"))
      (node (ref "C35") (pin "2") (pinfunction "2_2") (pintype "passive"))
      (node (ref "R22") (pin "2") (pinfunction "2_2") (pintype "passive"))
      (node (ref "U4") (pin "A1") (pinfunction "OUT_A_A1") (pintype "output"))
    )
    (net (code "53") (name "Net-(U4B-IN-)") (class "Default")
      (node (ref "C34") (pin "1") (pinfunction "1_1") (pintype "passive"))
      (node (ref "R32") (pin "1") (pinfunction "1_1") (pintype "passive"))
      (node (ref "R36") (pin "2") (pinfunction "2_2") (pintype "passive"))
      (node (ref "U4") (pin "C2") (pinfunction "IN-_C2") (pintype "input"))
    )
    (net (code "54") (name "Net-(U4B-OUT)") (class "Default")
      (node (ref "C23") (pin "1") (pinfunction "1_1") (pintype "passive"))
      (node (ref "C34") (pin "2") (pinfunction "2_2") (pintype "passive"))
      (node (ref "R32") (pin "2") (pinfunction "2_2") (pintype "passive"))
      (node (ref "U4") (pin "B2") (pinfunction "OUT_B2") (pintype "output"))
    )
    (net (code "55") (name "Net-(U6A-+INA)") (class "Default")
      (node (ref "C14") (pin "1") (pinfunction "1_1") (pintype "passive"))
      (node (ref "R18") (pin "2") (pinfunction "2_2") (pintype "passive"))
      (node (ref "R20") (pin "1") (pinfunction "1_1") (pintype "passive"))
      (node (ref "U6") (pin "C1") (pinfunction "+INA_C1") (pintype "input"))
    )
    (net (code "56") (name "Net-(U6A--INA)") (class "Default")
      (node (ref "R44") (pin "1") (pinfunction "1_1") (pintype "passive"))
      (node (ref "U6") (pin "A1") (pinfunction "OUT_A_A1") (pintype "output"))
      (node (ref "U6") (pin "B1") (pinfunction "-INA_B1") (pintype "input"))
    )
    (net (code "57") (name "VDD_3V3") (class "Default")
      (node (ref "C28") (pin "1") (pinfunction "1_1") (pintype "passive"))
      (node (ref "D2") (pin "1") (pinfunction "A_1") (pintype "passive"))
      (node (ref "D4") (pin "1") (pinfunction "A_1") (pintype "passive"))
      (node (ref "D5") (pin "1") (pinfunction "A_1") (pintype "passive"))
      (node (ref "R2") (pin "1") (pinfunction "1_1") (pintype "passive"))
      (node (ref "U5") (pin "5") (pinfunction "OUT2_5") (pintype "power_in"))
    )
    (net (code "58") (name "unconnected-(U2-P2.7{slash}P2.8-Pad1)") (class "Default")
      (node (ref "U2") (pin "1") (pinfunction "P2.7/P2.8_1") (pintype "input+no_connect"))
    )
    (net (code "59") (name "unconnected-(U2-P2.10-Pad3)") (class "Default")
      (node (ref "U2") (pin "3") (pinfunction "P2.10_3") (pintype "bidirectional"))
    )
    (net (code "60") (name "unconnected-(U6B-IN+-PadD2)") (class "Default")
      (node (ref "U6") (pin "D2") (pinfunction "IN+_D2") (pintype "input+no_connect"))
    )
    (net (code "61") (name "unconnected-(U6B-IN--PadC2)") (class "Default")
      (node (ref "U6") (pin "C2") (pinfunction "IN-_C2") (pintype "input+no_connect"))
    )
    (net (code "62") (name "unconnected-(U6B-OUT-PadB2)") (class "Default")
      (node (ref "U6") (pin "B2") (pinfunction "OUT_B2") (pintype "output"))
    )
  )
)
